# stm32f4_fc_simplified.net
KiCad netlist of a schematic drawn in EAGLE
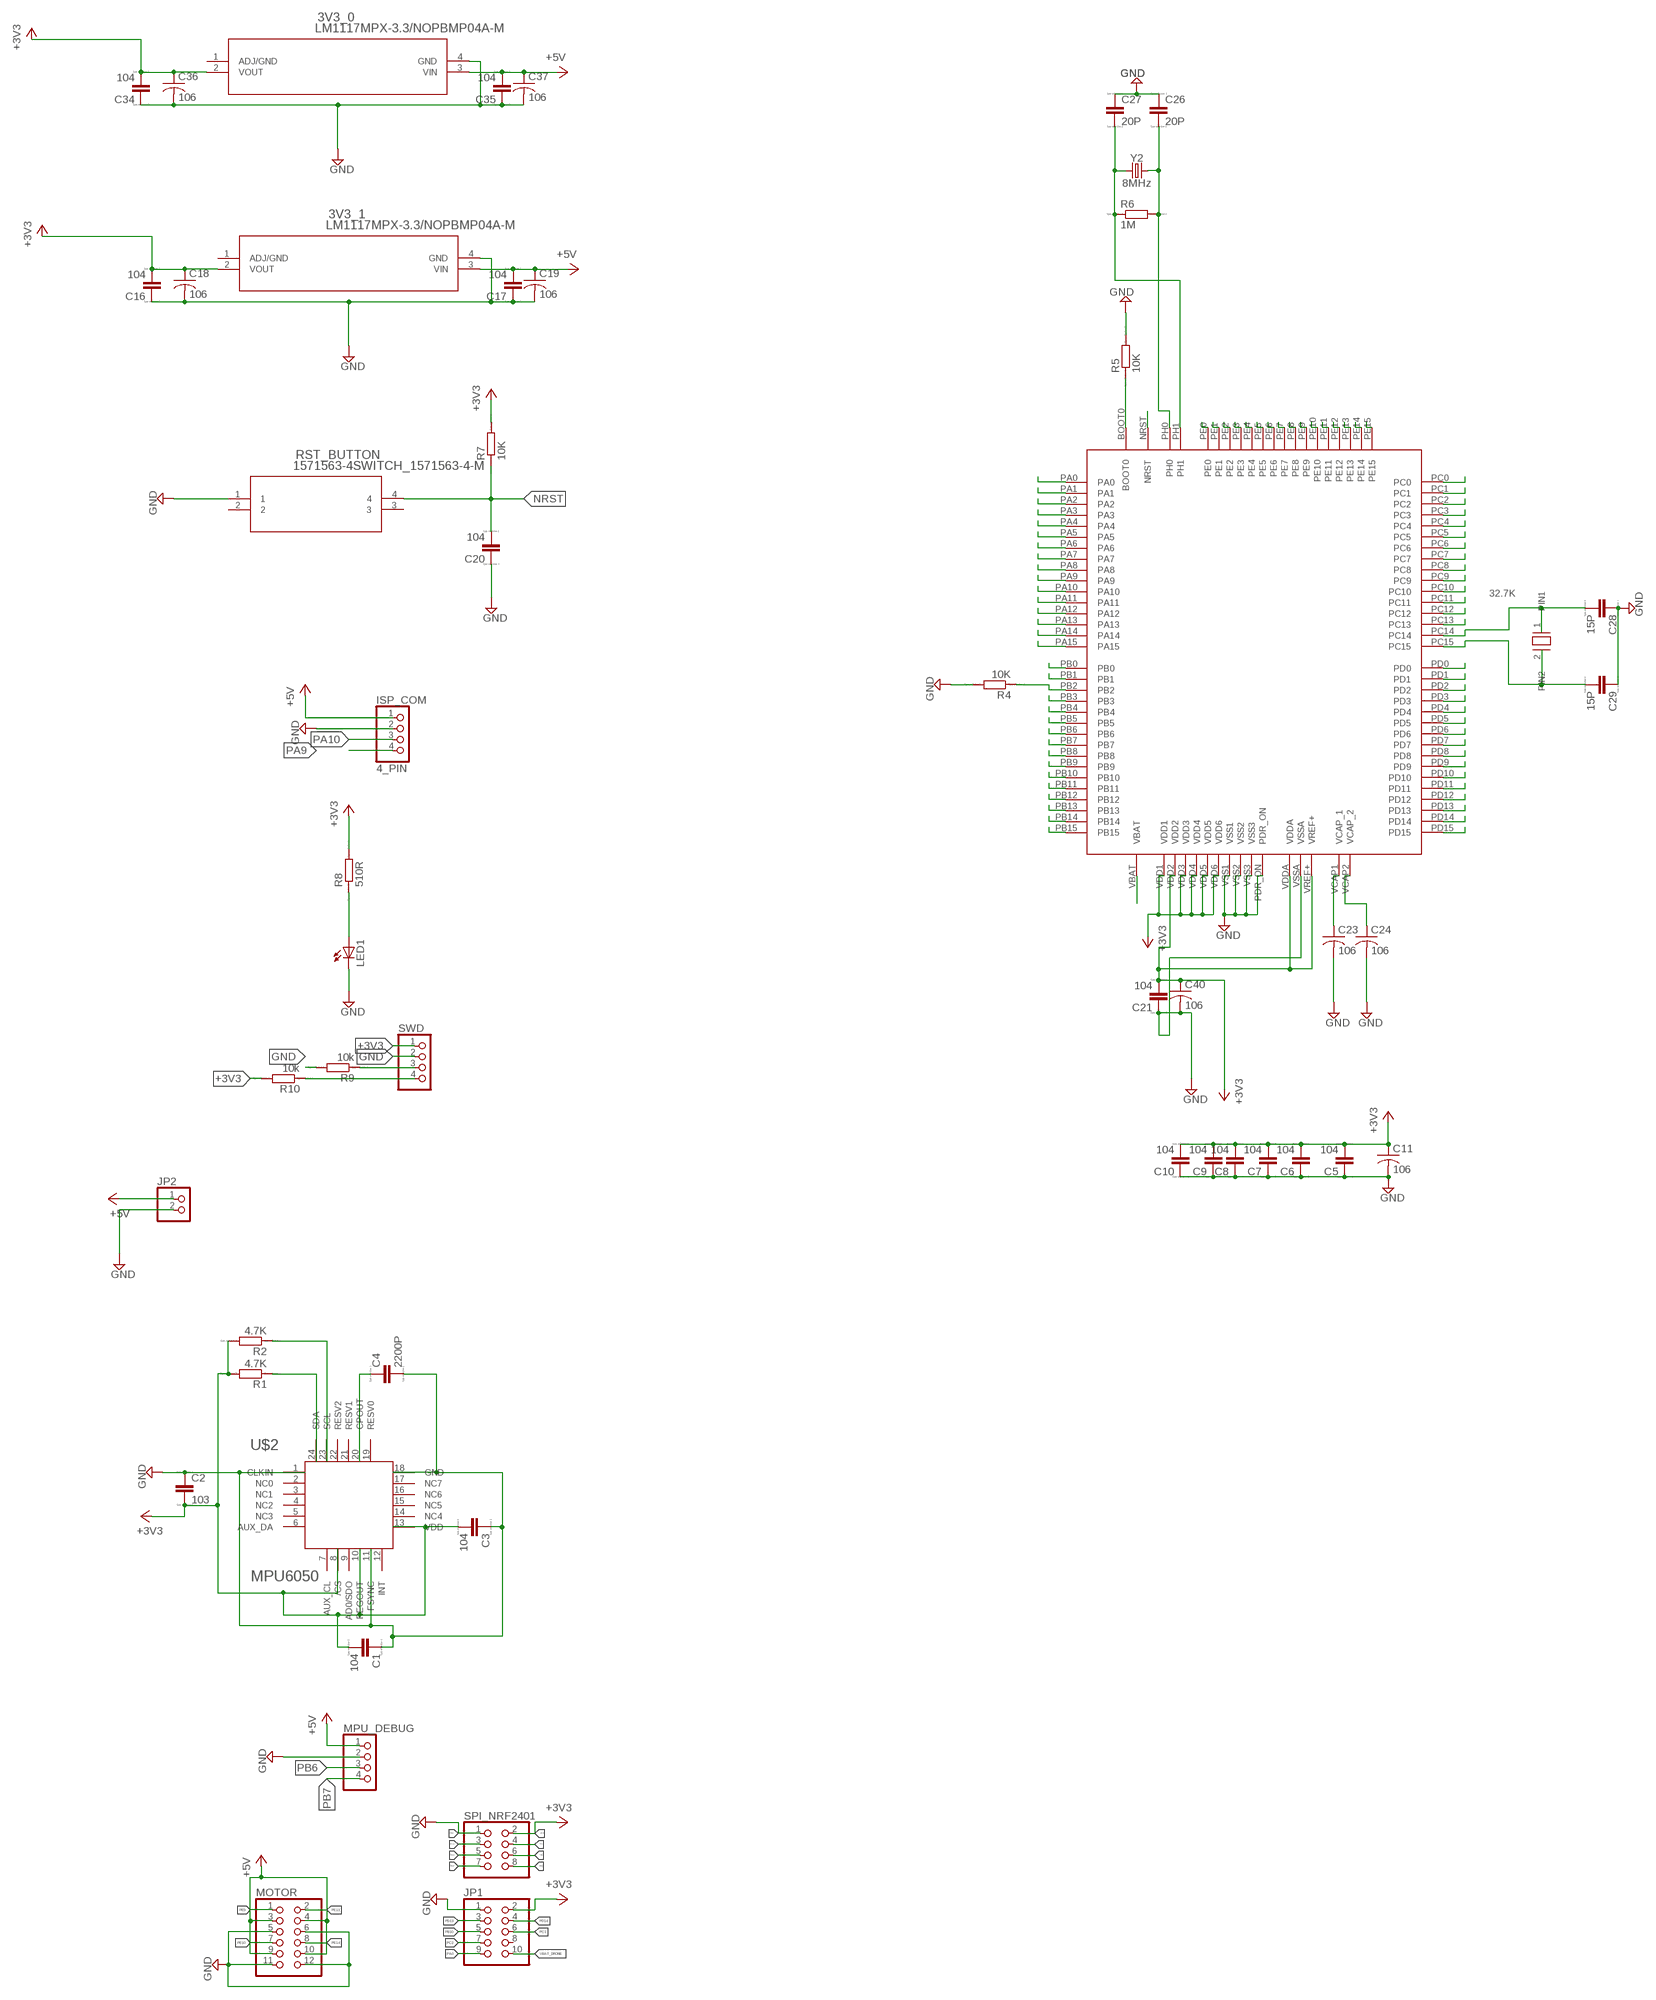
[diagram p0: schematic, sheet 1]

(export (version "E")
  (design (tool "Eeschema 10.0.6"))
  (components
    (comp (ref "3V3_0")
      (value "LM1117MPX-3.3/NOPBMP04A-M")
      (footprint "eagle-import:MP04A-M")
      (fields (field (name "MANUFACTURER_PART_NUMBER") "LM1117MPX3.3NOPB"))
      (libsource (lib "eagle-import") (part "LM1117MPX-3.3/NOPBMP04A-M"))
    )
    (comp (ref "3V3_1")
      (value "LM1117MPX-3.3/NOPBMP04A-M")
      (footprint "eagle-import:MP04A-M")
      (fields (field (name "MANUFACTURER_PART_NUMBER") "LM1117MPX3.3NOPB"))
      (libsource (lib "eagle-import") (part "LM1117MPX-3.3/NOPBMP04A-M"))
    )
    (comp (ref "32.7K")
      (value "CM315D")
      (footprint "eagle-import:CM315D_32.7K")
      (libsource (lib "eagle-import") (part "CM315D"))
    )
    (comp (ref "C1")
      (value "104")
      (footprint "eagle-import:C0603")
      (libsource (lib "eagle-import") (part "CC0603"))
    )
    (comp (ref "C2")
      (value "103")
      (footprint "eagle-import:C0603")
      (libsource (lib "eagle-import") (part "CC0603"))
    )
    (comp (ref "C3")
      (value "104")
      (footprint "eagle-import:C0603")
      (libsource (lib "eagle-import") (part "CC0603"))
    )
    (comp (ref "C4")
      (value "2200P")
      (footprint "eagle-import:C0603")
      (libsource (lib "eagle-import") (part "CC0603"))
    )
    (comp (ref "C5")
      (value "104")
      (footprint "eagle-import:C0603")
      (libsource (lib "eagle-import") (part "CC0603"))
    )
    (comp (ref "C6")
      (value "104")
      (footprint "eagle-import:C0603")
      (libsource (lib "eagle-import") (part "CC0603"))
    )
    (comp (ref "C7")
      (value "104")
      (footprint "eagle-import:C0603")
      (libsource (lib "eagle-import") (part "CC0603"))
    )
    (comp (ref "C8")
      (value "104")
      (footprint "eagle-import:C0603")
      (libsource (lib "eagle-import") (part "CC0603"))
    )
    (comp (ref "C9")
      (value "104")
      (footprint "eagle-import:C0603")
      (libsource (lib "eagle-import") (part "CC0603"))
    )
    (comp (ref "C10")
      (value "104")
      (footprint "eagle-import:C0603")
      (libsource (lib "eagle-import") (part "CC0603"))
    )
    (comp (ref "C11")
      (value "106")
      (footprint "eagle-import:C0805")
      (libsource (lib "eagle-import") (part "C-USC0805"))
    )
    (comp (ref "C16")
      (value "104")
      (footprint "eagle-import:C0603")
      (libsource (lib "eagle-import") (part "CC0603"))
    )
    (comp (ref "C17")
      (value "104")
      (footprint "eagle-import:C0603")
      (libsource (lib "eagle-import") (part "CC0603"))
    )
    (comp (ref "C18")
      (value "106")
      (footprint "eagle-import:C0805")
      (libsource (lib "eagle-import") (part "C-USC0805"))
    )
    (comp (ref "C19")
      (value "106")
      (footprint "eagle-import:C0805")
      (libsource (lib "eagle-import") (part "C-USC0805"))
    )
    (comp (ref "C20")
      (value "104")
      (footprint "eagle-import:C0603")
      (libsource (lib "eagle-import") (part "CC0603"))
    )
    (comp (ref "C21")
      (value "104")
      (footprint "eagle-import:C0603")
      (libsource (lib "eagle-import") (part "CC0603"))
    )
    (comp (ref "C23")
      (value "106")
      (footprint "eagle-import:C0805")
      (libsource (lib "eagle-import") (part "C-USC0805"))
    )
    (comp (ref "C24")
      (value "106")
      (footprint "eagle-import:C0805")
      (libsource (lib "eagle-import") (part "C-USC0805"))
    )
    (comp (ref "C26")
      (value "20P")
      (footprint "eagle-import:C0603")
      (libsource (lib "eagle-import") (part "CC0603"))
    )
    (comp (ref "C27")
      (value "20P")
      (footprint "eagle-import:C0603")
      (libsource (lib "eagle-import") (part "CC0603"))
    )
    (comp (ref "C28")
      (value "15P")
      (footprint "eagle-import:C0603")
      (libsource (lib "eagle-import") (part "CC0603"))
    )
    (comp (ref "C29")
      (value "15P")
      (footprint "eagle-import:C0603")
      (libsource (lib "eagle-import") (part "CC0603"))
    )
    (comp (ref "C34")
      (value "104")
      (footprint "eagle-import:C0603")
      (libsource (lib "eagle-import") (part "CC0603"))
    )
    (comp (ref "C35")
      (value "104")
      (footprint "eagle-import:C0603")
      (libsource (lib "eagle-import") (part "CC0603"))
    )
    (comp (ref "C36")
      (value "106")
      (footprint "eagle-import:C0805")
      (libsource (lib "eagle-import") (part "C-USC0805"))
    )
    (comp (ref "C37")
      (value "106")
      (footprint "eagle-import:C0805")
      (libsource (lib "eagle-import") (part "C-USC0805"))
    )
    (comp (ref "C40")
      (value "106")
      (footprint "eagle-import:C0805")
      (libsource (lib "eagle-import") (part "C-USC0805"))
    )
    (comp (ref "ISP_COM")
      (value "4_PIN")
      (footprint "eagle-import:1X04")
      (libsource (lib "eagle-import") (part "PINHD-1X4"))
    )
    (comp (ref "JP1")
      (value "PINHD-2X5/90")
      (footprint "eagle-import:2X05_90")
      (libsource (lib "eagle-import") (part "PINHD-2X5/90"))
    )
    (comp (ref "JP2")
      (value "PINHD-1X2")
      (footprint "eagle-import:1X02")
      (libsource (lib "eagle-import") (part "PINHD-1X2"))
    )
    (comp (ref "LED1")
      (value "LEDCHIPLED_0805")
      (footprint "eagle-import:CHIPLED_0805")
      (libsource (lib "eagle-import") (part "LEDCHIPLED_0805"))
    )
    (comp (ref "MOTOR")
      (value "PINHD-2X6/90")
      (footprint "eagle-import:2X06_90")
      (libsource (lib "eagle-import") (part "PINHD-2X6/90"))
    )
    (comp (ref "MPU_DEBUG")
      (value "PINHD-1X4")
      (footprint "eagle-import:1X04")
      (libsource (lib "eagle-import") (part "PINHD-1X4"))
    )
    (comp (ref "R1")
      (value "4.7K")
      (footprint "eagle-import:R0603")
      (libsource (lib "eagle-import") (part "RR0603"))
    )
    (comp (ref "R2")
      (value "4.7K")
      (footprint "eagle-import:R0603")
      (libsource (lib "eagle-import") (part "RR0603"))
    )
    (comp (ref "R4")
      (value "10K")
      (footprint "eagle-import:R0603")
      (libsource (lib "eagle-import") (part "RR0603"))
    )
    (comp (ref "R5")
      (value "10K")
      (footprint "eagle-import:R0603")
      (libsource (lib "eagle-import") (part "RR0603"))
    )
    (comp (ref "R6")
      (value "1M")
      (footprint "eagle-import:R0603")
      (libsource (lib "eagle-import") (part "RR0603"))
    )
    (comp (ref "R7")
      (value "10K")
      (footprint "eagle-import:R0603")
      (libsource (lib "eagle-import") (part "RR0603"))
    )
    (comp (ref "R8")
      (value "510R")
      (footprint "eagle-import:R0603")
      (libsource (lib "eagle-import") (part "RR0603"))
    )
    (comp (ref "R9")
      (value "10k")
      (footprint "eagle-import:R0603")
      (libsource (lib "eagle-import") (part "RR0603"))
    )
    (comp (ref "R10")
      (value "10k")
      (footprint "eagle-import:R0603")
      (libsource (lib "eagle-import") (part "RR0603"))
    )
    (comp (ref "RST_BUTTON")
      (value "1571563-4SWITCH_1571563-4-M")
      (footprint "eagle-import:SWITCH_1571563-4-M")
      (fields (field (name "MANUFACTURER_PART_NUMBER") "15715634"))
      (libsource (lib "eagle-import") (part "1571563-4SWITCH_1571563-4-M"))
    )
    (comp (ref "SPI_NRF2401")
      (value "PINHD-2X4")
      (footprint "eagle-import:2X04")
      (libsource (lib "eagle-import") (part "PINHD-2X4"))
    )
    (comp (ref "SWD")
      (value "PINHD-1X4")
      (footprint "eagle-import:1X04")
      (libsource (lib "eagle-import") (part "PINHD-1X4"))
    )
    (comp (ref "U$1")
      (value "STM32F4V_100PIN_GENERIC")
      (footprint "eagle-import:LQFP100")
      (libsource (lib "eagle-import") (part "STM32F4V_100PIN_GENERIC"))
    )
    (comp (ref "U$2")
      (value "MPU6050")
      (footprint "eagle-import:MPU6050")
      (libsource (lib "eagle-import") (part "MPU6050"))
    )
    (comp (ref "Y2")
      (value "8MHz")
      (footprint "eagle-import:HC49UP")
      (libsource (lib "eagle-import") (part "CRYSTAL-8MHZSMD-HC49UP"))
    )
  )
  (nets
    (net (code "1") (name "+3V3") (class "Default")
      (node (ref "3V3_0") (pin "2") (pinfunction "VOUT_2") (pintype "passive"))
      (node (ref "3V3_1") (pin "2") (pinfunction "VOUT_2") (pintype "passive"))
      (node (ref "C1") (pin "2") (pinfunction "2_2") (pintype "passive"))
      (node (ref "C10") (pin "2") (pinfunction "2_2") (pintype "passive"))
      (node (ref "C11") (pin "1") (pinfunction "1_1") (pintype "passive"))
      (node (ref "C16") (pin "2") (pinfunction "2_2") (pintype "passive"))
      (node (ref "C18") (pin "1") (pinfunction "1_1") (pintype "passive"))
      (node (ref "C2") (pin "2") (pinfunction "2_2") (pintype "passive"))
      (node (ref "C21") (pin "2") (pinfunction "2_2") (pintype "passive"))
      (node (ref "C3") (pin "2") (pinfunction "2_2") (pintype "passive"))
      (node (ref "C34") (pin "2") (pinfunction "2_2") (pintype "passive"))
      (node (ref "C36") (pin "1") (pinfunction "1_1") (pintype "passive"))
      (node (ref "C40") (pin "1") (pinfunction "1_1") (pintype "passive"))
      (node (ref "C5") (pin "2") (pinfunction "2_2") (pintype "passive"))
      (node (ref "C6") (pin "2") (pinfunction "2_2") (pintype "passive"))
      (node (ref "C7") (pin "2") (pinfunction "2_2") (pintype "passive"))
      (node (ref "C8") (pin "2") (pinfunction "2_2") (pintype "passive"))
      (node (ref "C9") (pin "2") (pinfunction "2_2") (pintype "passive"))
      (node (ref "JP1") (pin "2") (pinfunction "2_2") (pintype "passive"))
      (node (ref "R1") (pin "2") (pinfunction "2_2") (pintype "passive"))
      (node (ref "R10") (pin "2") (pinfunction "2_2") (pintype "passive"))
      (node (ref "R2") (pin "2") (pinfunction "2_2") (pintype "passive"))
      (node (ref "R7") (pin "2") (pinfunction "2_2") (pintype "passive"))
      (node (ref "R8") (pin "2") (pinfunction "2_2") (pintype "passive"))
      (node (ref "SPI_NRF2401") (pin "2") (pinfunction "2_2") (pintype "passive"))
      (node (ref "SWD") (pin "1") (pinfunction "1_1") (pintype "passive"))
      (node (ref "U$1") (pin "VDD1") (pinfunction "VDD1_VDD1") (pintype "bidirectional"))
      (node (ref "U$1") (pin "VDD2") (pinfunction "VDD2_VDD2") (pintype "bidirectional"))
      (node (ref "U$1") (pin "VDD3") (pinfunction "VDD3_VDD3") (pintype "bidirectional"))
      (node (ref "U$1") (pin "VDD4") (pinfunction "VDD4_VDD4") (pintype "bidirectional"))
      (node (ref "U$1") (pin "VDD5") (pinfunction "VDD5_VDD5") (pintype "bidirectional"))
      (node (ref "U$1") (pin "VDD6") (pinfunction "VDD6_VDD6") (pintype "bidirectional"))
      (node (ref "U$1") (pin "VDDA") (pinfunction "VDDA_VDDA") (pintype "bidirectional"))
      (node (ref "U$1") (pin "VREF+") (pinfunction "VREF+_VREF+") (pintype "bidirectional"))
      (node (ref "U$2") (pin "10") (pinfunction "REGOUT_10") (pintype "bidirectional"))
      (node (ref "U$2") (pin "13") (pinfunction "VDD_13") (pintype "bidirectional"))
      (node (ref "U$2") (pin "8") (pinfunction "/CS_8") (pintype "bidirectional"))
    )
    (net (code "2") (name "+5V") (class "Default")
      (node (ref "3V3_0") (pin "3") (pinfunction "VIN_3") (pintype "input"))
      (node (ref "3V3_1") (pin "3") (pinfunction "VIN_3") (pintype "input"))
      (node (ref "C17") (pin "2") (pinfunction "2_2") (pintype "passive"))
      (node (ref "C19") (pin "1") (pinfunction "1_1") (pintype "passive"))
      (node (ref "C35") (pin "2") (pinfunction "2_2") (pintype "passive"))
      (node (ref "C37") (pin "1") (pinfunction "1_1") (pintype "passive"))
      (node (ref "ISP_COM") (pin "1") (pinfunction "1_1") (pintype "passive"))
      (node (ref "JP2") (pin "1") (pinfunction "1_1") (pintype "passive"))
      (node (ref "MOTOR") (pin "10") (pinfunction "10_10") (pintype "passive"))
      (node (ref "MOTOR") (pin "3") (pinfunction "3_3") (pintype "passive"))
      (node (ref "MOTOR") (pin "4") (pinfunction "4_4") (pintype "passive"))
      (node (ref "MOTOR") (pin "9") (pinfunction "9_9") (pintype "passive"))
      (node (ref "MPU_DEBUG") (pin "1") (pinfunction "1_1") (pintype "passive"))
    )
    (net (code "3") (name "/PA13") (class "Default")
      (node (ref "R10") (pin "1") (pinfunction "1_1") (pintype "passive"))
      (node (ref "SWD") (pin "4") (pinfunction "4_4") (pintype "passive"))
      (node (ref "U$1") (pin "PA13") (pinfunction "PA13_PA13") (pintype "bidirectional"))
    )
    (net (code "4") (name "/PA14") (class "Default")
      (node (ref "R9") (pin "1") (pinfunction "1_1") (pintype "passive"))
      (node (ref "SWD") (pin "3") (pinfunction "3_3") (pintype "passive"))
      (node (ref "U$1") (pin "PA14") (pinfunction "PA14_PA14") (pintype "bidirectional"))
    )
    (net (code "5") (name "GND") (class "Default")
      (node (ref "3V3_0") (pin "4") (pinfunction "GND_4") (pintype "power_in"))
      (node (ref "3V3_1") (pin "4") (pinfunction "GND_4") (pintype "power_in"))
      (node (ref "C1") (pin "1") (pinfunction "1_1") (pintype "passive"))
      (node (ref "C10") (pin "1") (pinfunction "1_1") (pintype "passive"))
      (node (ref "C11") (pin "2") (pinfunction "2_2") (pintype "passive"))
      (node (ref "C16") (pin "1") (pinfunction "1_1") (pintype "passive"))
      (node (ref "C17") (pin "1") (pinfunction "1_1") (pintype "passive"))
      (node (ref "C18") (pin "2") (pinfunction "2_2") (pintype "passive"))
      (node (ref "C19") (pin "2") (pinfunction "2_2") (pintype "passive"))
      (node (ref "C2") (pin "1") (pinfunction "1_1") (pintype "passive"))
      (node (ref "C20") (pin "1") (pinfunction "1_1") (pintype "passive"))
      (node (ref "C21") (pin "1") (pinfunction "1_1") (pintype "passive"))
      (node (ref "C23") (pin "2") (pinfunction "2_2") (pintype "passive"))
      (node (ref "C24") (pin "2") (pinfunction "2_2") (pintype "passive"))
      (node (ref "C26") (pin "1") (pinfunction "1_1") (pintype "passive"))
      (node (ref "C27") (pin "1") (pinfunction "1_1") (pintype "passive"))
      (node (ref "C28") (pin "1") (pinfunction "1_1") (pintype "passive"))
      (node (ref "C29") (pin "1") (pinfunction "1_1") (pintype "passive"))
      (node (ref "C3") (pin "1") (pinfunction "1_1") (pintype "passive"))
      (node (ref "C34") (pin "1") (pinfunction "1_1") (pintype "passive"))
      (node (ref "C35") (pin "1") (pinfunction "1_1") (pintype "passive"))
      (node (ref "C36") (pin "2") (pinfunction "2_2") (pintype "passive"))
      (node (ref "C37") (pin "2") (pinfunction "2_2") (pintype "passive"))
      (node (ref "C4") (pin "2") (pinfunction "2_2") (pintype "passive"))
      (node (ref "C40") (pin "2") (pinfunction "2_2") (pintype "passive"))
      (node (ref "C5") (pin "1") (pinfunction "1_1") (pintype "passive"))
      (node (ref "C6") (pin "1") (pinfunction "1_1") (pintype "passive"))
      (node (ref "C7") (pin "1") (pinfunction "1_1") (pintype "passive"))
      (node (ref "C8") (pin "1") (pinfunction "1_1") (pintype "passive"))
      (node (ref "C9") (pin "1") (pinfunction "1_1") (pintype "passive"))
      (node (ref "ISP_COM") (pin "2") (pinfunction "2_2") (pintype "passive"))
      (node (ref "JP1") (pin "1") (pinfunction "1_1") (pintype "passive"))
      (node (ref "JP2") (pin "2") (pinfunction "2_2") (pintype "passive"))
      (node (ref "LED1") (pin "C") (pinfunction "C_C") (pintype "passive"))
      (node (ref "MOTOR") (pin "11") (pinfunction "11_11") (pintype "passive"))
      (node (ref "MOTOR") (pin "12") (pinfunction "12_12") (pintype "passive"))
      (node (ref "MOTOR") (pin "5") (pinfunction "5_5") (pintype "passive"))
      (node (ref "MOTOR") (pin "6") (pinfunction "6_6") (pintype "passive"))
      (node (ref "MPU_DEBUG") (pin "2") (pinfunction "2_2") (pintype "passive"))
      (node (ref "R4") (pin "2") (pinfunction "2_2") (pintype "passive"))
      (node (ref "R5") (pin "2") (pinfunction "2_2") (pintype "passive"))
      (node (ref "R9") (pin "2") (pinfunction "2_2") (pintype "passive"))
      (node (ref "RST_BUTTON") (pin "1") (pinfunction "1_1") (pintype "passive"))
      (node (ref "SPI_NRF2401") (pin "1") (pinfunction "1_1") (pintype "passive"))
      (node (ref "SWD") (pin "2") (pinfunction "2_2") (pintype "passive"))
      (node (ref "U$1") (pin "PDR_ON") (pinfunction "PDR_ON_PDR_ON") (pintype "bidirectional"))
      (node (ref "U$1") (pin "VSS1") (pinfunction "VSS1_VSS1") (pintype "bidirectional"))
      (node (ref "U$1") (pin "VSS2") (pinfunction "VSS2_VSS2") (pintype "bidirectional"))
      (node (ref "U$1") (pin "VSS3") (pinfunction "VSS3_VSS3") (pintype "bidirectional"))
      (node (ref "U$1") (pin "VSSA") (pinfunction "VSSA_VSSA") (pintype "bidirectional"))
      (node (ref "U$2") (pin "1") (pinfunction "CLKIN_1") (pintype "bidirectional"))
      (node (ref "U$2") (pin "11") (pinfunction "FSYNC_11") (pintype "bidirectional"))
      (node (ref "U$2") (pin "18") (pinfunction "GND_18") (pintype "bidirectional"))
    )
    (net (code "6") (name "IRQ") (class "Default")
      (node (ref "SPI_NRF2401") (pin "8") (pinfunction "8_8") (pintype "passive"))
    )
    (net (code "7") (name "NRST") (class "Default")
      (node (ref "C20") (pin "2") (pinfunction "2_2") (pintype "passive"))
      (node (ref "R7") (pin "1") (pinfunction "1_1") (pintype "passive"))
      (node (ref "RST_BUTTON") (pin "4") (pinfunction "4_4") (pintype "passive"))
      (node (ref "U$1") (pin "NRST") (pinfunction "NRST_NRST") (pintype "bidirectional"))
    )
    (net (code "8") (name "Net-(32.7K-PIN1)") (class "Default")
      (node (ref "32.7K") (pin "1") (pinfunction "PIN1_1") (pintype "bidirectional"))
      (node (ref "C28") (pin "2") (pinfunction "2_2") (pintype "passive"))
      (node (ref "U$1") (pin "PC14") (pinfunction "PC14_PC14") (pintype "bidirectional"))
    )
    (net (code "9") (name "Net-(32.7K-PIN2)") (class "Default")
      (node (ref "32.7K") (pin "2") (pinfunction "PIN2_2") (pintype "bidirectional"))
      (node (ref "C29") (pin "2") (pinfunction "2_2") (pintype "passive"))
      (node (ref "U$1") (pin "PC15") (pinfunction "PC15_PC15") (pintype "bidirectional"))
    )
    (net (code "10") (name "Net-(C26-Pad2)") (class "Default")
      (node (ref "C26") (pin "2") (pinfunction "2_2") (pintype "passive"))
      (node (ref "R6") (pin "2") (pinfunction "2_2") (pintype "passive"))
      (node (ref "U$1") (pin "PH0") (pinfunction "PH0_PH0") (pintype "bidirectional"))
      (node (ref "Y2") (pin "2") (pinfunction "2_2") (pintype "passive"))
    )
    (net (code "11") (name "Net-(C27-Pad2)") (class "Default")
      (node (ref "C27") (pin "2") (pinfunction "2_2") (pintype "passive"))
      (node (ref "R6") (pin "1") (pinfunction "1_1") (pintype "passive"))
      (node (ref "U$1") (pin "PH1") (pinfunction "PH1_PH1") (pintype "bidirectional"))
      (node (ref "Y2") (pin "1") (pinfunction "1_1") (pintype "passive"))
    )
    (net (code "12") (name "Net-(LED1-PadA)") (class "Default")
      (node (ref "LED1") (pin "A") (pinfunction "A_A") (pintype "passive"))
      (node (ref "R8") (pin "1") (pinfunction "1_1") (pintype "passive"))
    )
    (net (code "13") (name "Net-(R4-Pad1)") (class "Default")
      (node (ref "R4") (pin "1") (pinfunction "1_1") (pintype "passive"))
      (node (ref "U$1") (pin "PB2") (pinfunction "PB2_PB2") (pintype "bidirectional"))
    )
    (net (code "14") (name "Net-(R5-Pad1)") (class "Default")
      (node (ref "R5") (pin "1") (pinfunction "1_1") (pintype "passive"))
      (node (ref "U$1") (pin "BOOT0") (pinfunction "BOOT0_BOOT0") (pintype "bidirectional"))
    )
    (net (code "15") (name "Net-(U$1-VCAP_1)") (class "Default")
      (node (ref "C23") (pin "1") (pinfunction "1_1") (pintype "passive"))
      (node (ref "U$1") (pin "VCAP1") (pinfunction "VCAP_1_VCAP1") (pintype "bidirectional"))
    )
    (net (code "16") (name "Net-(U$1-VCAP_2)") (class "Default")
      (node (ref "C24") (pin "1") (pinfunction "1_1") (pintype "passive"))
      (node (ref "U$1") (pin "VCAP2") (pinfunction "VCAP_2_VCAP2") (pintype "bidirectional"))
    )
    (net (code "17") (name "Net-(U$2-CPOUT)") (class "Default")
      (node (ref "C4") (pin "1") (pinfunction "1_1") (pintype "passive"))
      (node (ref "U$2") (pin "20") (pinfunction "CPOUT_20") (pintype "bidirectional"))
    )
    (net (code "18") (name "PA0") (class "Default")
      (node (ref "JP1") (pin "9") (pinfunction "9_9") (pintype "passive"))
      (node (ref "U$1") (pin "PA0") (pinfunction "PA0_PA0") (pintype "bidirectional"))
    )
    (net (code "19") (name "PA5") (class "Default")
      (node (ref "SPI_NRF2401") (pin "5") (pinfunction "5_5") (pintype "passive"))
      (node (ref "U$1") (pin "PA5") (pinfunction "PA5_PA5") (pintype "bidirectional"))
    )
    (net (code "20") (name "PA6") (class "Default")
      (node (ref "SPI_NRF2401") (pin "7") (pinfunction "7_7") (pintype "passive"))
      (node (ref "U$1") (pin "PA6") (pinfunction "PA6_PA6") (pintype "bidirectional"))
    )
    (net (code "21") (name "PA7") (class "Default")
      (node (ref "SPI_NRF2401") (pin "6") (pinfunction "6_6") (pintype "passive"))
      (node (ref "U$1") (pin "PA7") (pinfunction "PA7_PA7") (pintype "bidirectional"))
    )
    (net (code "22") (name "PA9") (class "Default")
      (node (ref "ISP_COM") (pin "4") (pinfunction "4_4") (pintype "passive"))
      (node (ref "U$1") (pin "PA9") (pinfunction "PA9_PA9") (pintype "bidirectional"))
    )
    (net (code "23") (name "PA10") (class "Default")
      (node (ref "ISP_COM") (pin "3") (pinfunction "3_3") (pintype "passive"))
      (node (ref "U$1") (pin "PA10") (pinfunction "PA10_PA10") (pintype "bidirectional"))
    )
    (net (code "24") (name "PB6") (class "Default")
      (node (ref "MPU_DEBUG") (pin "3") (pinfunction "3_3") (pintype "passive"))
      (node (ref "R2") (pin "1") (pinfunction "1_1") (pintype "passive"))
      (node (ref "U$1") (pin "PB6") (pinfunction "PB6_PB6") (pintype "bidirectional"))
      (node (ref "U$2") (pin "23") (pinfunction "SCL_23") (pintype "bidirectional"))
    )
    (net (code "25") (name "PB7") (class "Default")
      (node (ref "MPU_DEBUG") (pin "4") (pinfunction "4_4") (pintype "passive"))
      (node (ref "R1") (pin "1") (pinfunction "1_1") (pintype "passive"))
      (node (ref "U$1") (pin "PB7") (pinfunction "PB7_PB7") (pintype "bidirectional"))
      (node (ref "U$2") (pin "24") (pinfunction "SDA_24") (pintype "bidirectional"))
    )
    (net (code "26") (name "PB10") (class "Default")
      (node (ref "JP1") (pin "5") (pinfunction "5_5") (pintype "passive"))
      (node (ref "U$1") (pin "PB10") (pinfunction "PB10_PB10") (pintype "bidirectional"))
    )
    (net (code "27") (name "PC2") (class "Default")
      (node (ref "JP1") (pin "7") (pinfunction "7_7") (pintype "passive"))
      (node (ref "U$1") (pin "PC2") (pinfunction "PC2_PC2") (pintype "bidirectional"))
    )
    (net (code "28") (name "PC3") (class "Default")
      (node (ref "JP1") (pin "6") (pinfunction "6_6") (pintype "passive"))
      (node (ref "U$1") (pin "PC3") (pinfunction "PC3_PC3") (pintype "bidirectional"))
    )
    (net (code "29") (name "PC4") (class "Default")
      (node (ref "SPI_NRF2401") (pin "3") (pinfunction "3_3") (pintype "passive"))
      (node (ref "U$1") (pin "PC4") (pinfunction "PC4_PC4") (pintype "bidirectional"))
    )
    (net (code "30") (name "PC5") (class "Default")
      (node (ref "SPI_NRF2401") (pin "4") (pinfunction "4_4") (pintype "passive"))
      (node (ref "U$1") (pin "PC5") (pinfunction "PC5_PC5") (pintype "bidirectional"))
    )
    (net (code "31") (name "PD13") (class "Default")
      (node (ref "JP1") (pin "3") (pinfunction "3_3") (pintype "passive"))
      (node (ref "U$1") (pin "PD13") (pinfunction "PD13_PD13") (pintype "bidirectional"))
    )
    (net (code "32") (name "PD14") (class "Default")
      (node (ref "JP1") (pin "4") (pinfunction "4_4") (pintype "passive"))
      (node (ref "U$1") (pin "PD14") (pinfunction "PD14_PD14") (pintype "bidirectional"))
    )
    (net (code "33") (name "PE9") (class "Default")
      (node (ref "MOTOR") (pin "1") (pinfunction "1_1") (pintype "passive"))
      (node (ref "U$1") (pin "PE9") (pinfunction "PE9_PE9") (pintype "bidirectional"))
    )
    (net (code "34") (name "PE10") (class "Default")
      (node (ref "MOTOR") (pin "7") (pinfunction "7_7") (pintype "passive"))
      (node (ref "U$1") (pin "PE10") (pinfunction "PE10_PE10") (pintype "bidirectional"))
    )
    (net (code "35") (name "PE13") (class "Default")
      (node (ref "MOTOR") (pin "2") (pinfunction "2_2") (pintype "passive"))
      (node (ref "U$1") (pin "PE13") (pinfunction "PE13_PE13") (pintype "bidirectional"))
    )
    (net (code "36") (name "PE14") (class "Default")
      (node (ref "MOTOR") (pin "8") (pinfunction "8_8") (pintype "passive"))
      (node (ref "U$1") (pin "PE14") (pinfunction "PE14_PE14") (pintype "bidirectional"))
    )
    (net (code "37") (name "VBAT_DRONE") (class "Default")
      (node (ref "JP1") (pin "10") (pinfunction "10_10") (pintype "passive"))
    )
    (net (code "38") (name "unconnected-(3V3_0-ADJ{slash}GND-Pad1)") (class "Default")
      (node (ref "3V3_0") (pin "1") (pinfunction "ADJ/GND_1") (pintype "passive"))
    )
    (net (code "39") (name "unconnected-(3V3_1-ADJ{slash}GND-Pad1)") (class "Default")
      (node (ref "3V3_1") (pin "1") (pinfunction "ADJ/GND_1") (pintype "passive"))
    )
    (net (code "40") (name "unconnected-(JP1-Pad8)") (class "Default")
      (node (ref "JP1") (pin "8") (pinfunction "8_8") (pintype "passive"))
    )
    (net (code "41") (name "unconnected-(RST_BUTTON-Pad2)") (class "Default")
      (node (ref "RST_BUTTON") (pin "2") (pinfunction "2_2") (pintype "passive"))
    )
    (net (code "42") (name "unconnected-(RST_BUTTON-Pad3)") (class "Default")
      (node (ref "RST_BUTTON") (pin "3") (pinfunction "3_3") (pintype "passive"))
    )
    (net (code "43") (name "unconnected-(U$1-PadPA1)") (class "Default")
      (node (ref "U$1") (pin "PA1") (pinfunction "PA1_PA1") (pintype "bidirectional"))
    )
    (net (code "44") (name "unconnected-(U$1-PadPA2)") (class "Default")
      (node (ref "U$1") (pin "PA2") (pinfunction "PA2_PA2") (pintype "bidirectional"))
    )
    (net (code "45") (name "unconnected-(U$1-PadPA3)") (class "Default")
      (node (ref "U$1") (pin "PA3") (pinfunction "PA3_PA3") (pintype "bidirectional"))
    )
    (net (code "46") (name "unconnected-(U$1-PadPA4)") (class "Default")
      (node (ref "U$1") (pin "PA4") (pinfunction "PA4_PA4") (pintype "bidirectional"))
    )
    (net (code "47") (name "unconnected-(U$1-PadPA8)") (class "Default")
      (node (ref "U$1") (pin "PA8") (pinfunction "PA8_PA8") (pintype "bidirectional"))
    )
    (net (code "48") (name "unconnected-(U$1-PadPA11)") (class "Default")
      (node (ref "U$1") (pin "PA11") (pinfunction "PA11_PA11") (pintype "bidirectional"))
    )
    (net (code "49") (name "unconnected-(U$1-PadPA12)") (class "Default")
      (node (ref "U$1") (pin "PA12") (pinfunction "PA12_PA12") (pintype "bidirectional"))
    )
    (net (code "50") (name "unconnected-(U$1-PadPA15)") (class "Default")
      (node (ref "U$1") (pin "PA15") (pinfunction "PA15_PA15") (pintype "bidirectional"))
    )
    (net (code "51") (name "unconnected-(U$1-PadPB0)") (class "Default")
      (node (ref "U$1") (pin "PB0") (pinfunction "PB0_PB0") (pintype "bidirectional"))
    )
    (net (code "52") (name "unconnected-(U$1-PadPB1)") (class "Default")
      (node (ref "U$1") (pin "PB1") (pinfunction "PB1_PB1") (pintype "bidirectional"))
    )
    (net (code "53") (name "unconnected-(U$1-PadPB3)") (class "Default")
      (node (ref "U$1") (pin "PB3") (pinfunction "PB3_PB3") (pintype "bidirectional"))
    )
    (net (code "54") (name "unconnected-(U$1-PadPB4)") (class "Default")
      (node (ref "U$1") (pin "PB4") (pinfunction "PB4_PB4") (pintype "bidirectional"))
    )
    (net (code "55") (name "unconnected-(U$1-PadPB5)") (class "Default")
      (node (ref "U$1") (pin "PB5") (pinfunction "PB5_PB5") (pintype "bidirectional"))
    )
    (net (code "56") (name "unconnected-(U$1-PadPB8)") (class "Default")
      (node (ref "U$1") (pin "PB8") (pinfunction "PB8_PB8") (pintype "bidirectional"))
    )
    (net (code "57") (name "unconnected-(U$1-PadPB9)") (class "Default")
      (node (ref "U$1") (pin "PB9") (pinfunction "PB9_PB9") (pintype "bidirectional"))
    )
    (net (code "58") (name "unconnected-(U$1-PadPB11)") (class "Default")
      (node (ref "U$1") (pin "PB11") (pinfunction "PB11_PB11") (pintype "bidirectional"))
    )
    (net (code "59") (name "unconnected-(U$1-PadPB12)") (class "Default")
      (node (ref "U$1") (pin "PB12") (pinfunction "PB12_PB12") (pintype "bidirectional"))
    )
    (net (code "60") (name "unconnected-(U$1-PadPB13)") (class "Default")
      (node (ref "U$1") (pin "PB13") (pinfunction "PB13_PB13") (pintype "bidirectional"))
    )
    (net (code "61") (name "unconnected-(U$1-PadPB14)") (class "Default")
      (node (ref "U$1") (pin "PB14") (pinfunction "PB14_PB14") (pintype "bidirectional"))
    )
    (net (code "62") (name "unconnected-(U$1-PadPB15)") (class "Default")
      (node (ref "U$1") (pin "PB15") (pinfunction "PB15_PB15") (pintype "bidirectional"))
    )
    (net (code "63") (name "unconnected-(U$1-PadPC0)") (class "Default")
      (node (ref "U$1") (pin "PC0") (pinfunction "PC0_PC0") (pintype "bidirectional"))
    )
    (net (code "64") (name "unconnected-(U$1-PadPC1)") (class "Default")
      (node (ref "U$1") (pin "PC1") (pinfunction "PC1_PC1") (pintype "bidirectional"))
    )
    (net (code "65") (name "unconnected-(U$1-PadPC6)") (class "Default")
      (node (ref "U$1") (pin "PC6") (pinfunction "PC6_PC6") (pintype "bidirectional"))
    )
    (net (code "66") (name "unconnected-(U$1-PadPC7)") (class "Default")
      (node (ref "U$1") (pin "PC7") (pinfunction "PC7_PC7") (pintype "bidirectional"))
    )
    (net (code "67") (name "unconnected-(U$1-PadPC8)") (class "Default")
      (node (ref "U$1") (pin "PC8") (pinfunction "PC8_PC8") (pintype "bidirectional"))
    )
    (net (code "68") (name "unconnected-(U$1-PadPC9)") (class "Default")
      (node (ref "U$1") (pin "PC9") (pinfunction "PC9_PC9") (pintype "bidirectional"))
    )
    (net (code "69") (name "unconnected-(U$1-PadPC10)") (class "Default")
      (node (ref "U$1") (pin "PC10") (pinfunction "PC10_PC10") (pintype "bidirectional"))
    )
    (net (code "70") (name "unconnected-(U$1-PadPC11)") (class "Default")
      (node (ref "U$1") (pin "PC11") (pinfunction "PC11_PC11") (pintype "bidirectional"))
    )
    (net (code "71") (name "unconnected-(U$1-PadPC12)") (class "Default")
      (node (ref "U$1") (pin "PC12") (pinfunction "PC12_PC12") (pintype "bidirectional"))
    )
    (net (code "72") (name "unconnected-(U$1-PadPC13)") (class "Default")
      (node (ref "U$1") (pin "PC13") (pinfunction "PC13_PC13") (pintype "bidirectional"))
    )
    (net (code "73") (name "unconnected-(U$1-PadPD0)") (class "Default")
      (node (ref "U$1") (pin "PD0") (pinfunction "PD0_PD0") (pintype "bidirectional"))
    )
    (net (code "74") (name "unconnected-(U$1-PadPD1)") (class "Default")
      (node (ref "U$1") (pin "PD1") (pinfunction "PD1_PD1") (pintype "bidirectional"))
    )
    (net (code "75") (name "unconnected-(U$1-PadPD2)") (class "Default")
      (node (ref "U$1") (pin "PD2") (pinfunction "PD2_PD2") (pintype "bidirectional"))
    )
    (net (code "76") (name "unconnected-(U$1-PadPD3)") (class "Default")
      (node (ref "U$1") (pin "PD3") (pinfunction "PD3_PD3") (pintype "bidirectional"))
    )
    (net (code "77") (name "unconnected-(U$1-PadPD4)") (class "Default")
      (node (ref "U$1") (pin "PD4") (pinfunction "PD4_PD4") (pintype "bidirectional"))
    )
    (net (code "78") (name "unconnected-(U$1-PadPD5)") (class "Default")
      (node (ref "U$1") (pin "PD5") (pinfunction "PD5_PD5") (pintype "bidirectional"))
    )
    (net (code "79") (name "unconnected-(U$1-PadPD6)") (class "Default")
      (node (ref "U$1") (pin "PD6") (pinfunction "PD6_PD6") (pintype "bidirectional"))
    )
    (net (code "80") (name "unconnected-(U$1-PadPD7)") (class "Default")
      (node (ref "U$1") (pin "PD7") (pinfunction "PD7_PD7") (pintype "bidirectional"))
    )
    (net (code "81") (name "unconnected-(U$1-PadPD8)") (class "Default")
      (node (ref "U$1") (pin "PD8") (pinfunction "PD8_PD8") (pintype "bidirectional"))
    )
    (net (code "82") (name "unconnected-(U$1-PadPD9)") (class "Default")
      (node (ref "U$1") (pin "PD9") (pinfunction "PD9_PD9") (pintype "bidirectional"))
    )
    (net (code "83") (name "unconnected-(U$1-PadPD10)") (class "Default")
      (node (ref "U$1") (pin "PD10") (pinfunction "PD10_PD10") (pintype "bidirectional"))
    )
    (net (code "84") (name "unconnected-(U$1-PadPD11)") (class "Default")
      (node (ref "U$1") (pin "PD11") (pinfunction "PD11_PD11") (pintype "bidirectional"))
    )
    (net (code "85") (name "unconnected-(U$1-PadPD12)") (class "Default")
      (node (ref "U$1") (pin "PD12") (pinfunction "PD12_PD12") (pintype "bidirectional"))
    )
    (net (code "86") (name "unconnected-(U$1-PadPD15)") (class "Default")
      (node (ref "U$1") (pin "PD15") (pinfunction "PD15_PD15") (pintype "bidirectional"))
    )
    (net (code "87") (name "unconnected-(U$1-PadPE0)") (class "Default")
      (node (ref "U$1") (pin "PE0") (pinfunction "PE0_PE0") (pintype "bidirectional"))
    )
    (net (code "88") (name "unconnected-(U$1-PadPE1)") (class "Default")
      (node (ref "U$1") (pin "PE1") (pinfunction "PE1_PE1") (pintype "bidirectional"))
    )
    (net (code "89") (name "unconnected-(U$1-PadPE2)") (class "Default")
      (node (ref "U$1") (pin "PE2") (pinfunction "PE2_PE2") (pintype "bidirectional"))
    )
    (net (code "90") (name "unconnected-(U$1-PadPE3)") (class "Default")
      (node (ref "U$1") (pin "PE3") (pinfunction "PE3_PE3") (pintype "bidirectional"))
    )
    (net (code "91") (name "unconnected-(U$1-PadPE4)") (class "Default")
      (node (ref "U$1") (pin "PE4") (pinfunction "PE4_PE4") (pintype "bidirectional"))
    )
    (net (code "92") (name "unconnected-(U$1-PadPE5)") (class "Default")
      (node (ref "U$1") (pin "PE5") (pinfunction "PE5_PE5") (pintype "bidirectional"))
    )
    (net (code "93") (name "unconnected-(U$1-PadPE6)") (class "Default")
      (node (ref "U$1") (pin "PE6") (pinfunction "PE6_PE6") (pintype "bidirectional"))
    )
    (net (code "94") (name "unconnected-(U$1-PadPE7)") (class "Default")
      (node (ref "U$1") (pin "PE7") (pinfunction "PE7_PE7") (pintype "bidirectional"))
    )
    (net (code "95") (name "unconnected-(U$1-PadPE8)") (class "Default")
      (node (ref "U$1") (pin "PE8") (pinfunction "PE8_PE8") (pintype "bidirectional"))
    )
    (net (code "96") (name "unconnected-(U$1-PadPE11)") (class "Default")
      (node (ref "U$1") (pin "PE11") (pinfunction "PE11_PE11") (pintype "bidirectional"))
    )
    (net (code "97") (name "unconnected-(U$1-PadPE12)") (class "Default")
      (node (ref "U$1") (pin "PE12") (pinfunction "PE12_PE12") (pintype "bidirectional"))
    )
    (net (code "98") (name "unconnected-(U$1-PadPE15)") (class "Default")
      (node (ref "U$1") (pin "PE15") (pinfunction "PE15_PE15") (pintype "bidirectional"))
    )
    (net (code "99") (name "unconnected-(U$1-PadVBAT)") (class "Default")
      (node (ref "U$1") (pin "VBAT") (pinfunction "VBAT_VBAT") (pintype "bidirectional"))
    )
    (net (code "100") (name "unconnected-(U$2-AD0{slash}SDO-Pad9)") (class "Default")
      (node (ref "U$2") (pin "9") (pinfunction "AD0/SDO_9") (pintype "bidirectional"))
    )
    (net (code "101") (name "unconnected-(U$2-AUX_CL-Pad7)") (class "Default")
      (node (ref "U$2") (pin "7") (pinfunction "AUX_CL_7") (pintype "bidirectional"))
    )
    (net (code "102") (name "unconnected-(U$2-AUX_DA-Pad6)") (class "Default")
      (node (ref "U$2") (pin "6") (pinfunction "AUX_DA_6") (pintype "bidirectional"))
    )
    (net (code "103") (name "unconnected-(U$2-INT-Pad12)") (class "Default")
      (node (ref "U$2") (pin "12") (pinfunction "INT_12") (pintype "bidirectional"))
    )
    (net (code "104") (name "unconnected-(U$2-NC0-Pad2)") (class "Default")
      (node (ref "U$2") (pin "2") (pinfunction "NC0_2") (pintype "bidirectional"))
    )
    (net (code "105") (name "unconnected-(U$2-NC1-Pad3)") (class "Default")
      (node (ref "U$2") (pin "3") (pinfunction "NC1_3") (pintype "bidirectional"))
    )
    (net (code "106") (name "unconnected-(U$2-NC2-Pad4)") (class "Default")
      (node (ref "U$2") (pin "4") (pinfunction "NC2_4") (pintype "bidirectional"))
    )
    (net (code "107") (name "unconnected-(U$2-NC3-Pad5)") (class "Default")
      (node (ref "U$2") (pin "5") (pinfunction "NC3_5") (pintype "bidirectional"))
    )
    (net (code "108") (name "unconnected-(U$2-NC4-Pad14)") (class "Default")
      (node (ref "U$2") (pin "14") (pinfunction "NC4_14") (pintype "bidirectional"))
    )
    (net (code "109") (name "unconnected-(U$2-NC5-Pad15)") (class "Default")
      (node (ref "U$2") (pin "15") (pinfunction "NC5_15") (pintype "bidirectional"))
    )
    (net (code "110") (name "unconnected-(U$2-NC6-Pad16)") (class "Default")
      (node (ref "U$2") (pin "16") (pinfunction "NC6_16") (pintype "bidirectional"))
    )
    (net (code "111") (name "unconnected-(U$2-NC7-Pad17)") (class "Default")
      (node (ref "U$2") (pin "17") (pinfunction "NC7_17") (pintype "bidirectional"))
    )
    (net (code "112") (name "unconnected-(U$2-RESV0-Pad19)") (class "Default")
      (node (ref "U$2") (pin "19") (pinfunction "RESV0_19") (pintype "bidirectional"))
    )
    (net (code "113") (name "unconnected-(U$2-RESV1-Pad21)") (class "Default")
      (node (ref "U$2") (pin "21") (pinfunction "RESV1_21") (pintype "bidirectional"))
    )
    (net (code "114") (name "unconnected-(U$2-RESV2-Pad22)") (class "Default")
      (node (ref "U$2") (pin "22") (pinfunction "RESV2_22") (pintype "bidirectional"))
    )
  )
)
